# Lamp_C_Unit.net
KiCad netlist of a schematic drawn in Altium Designer
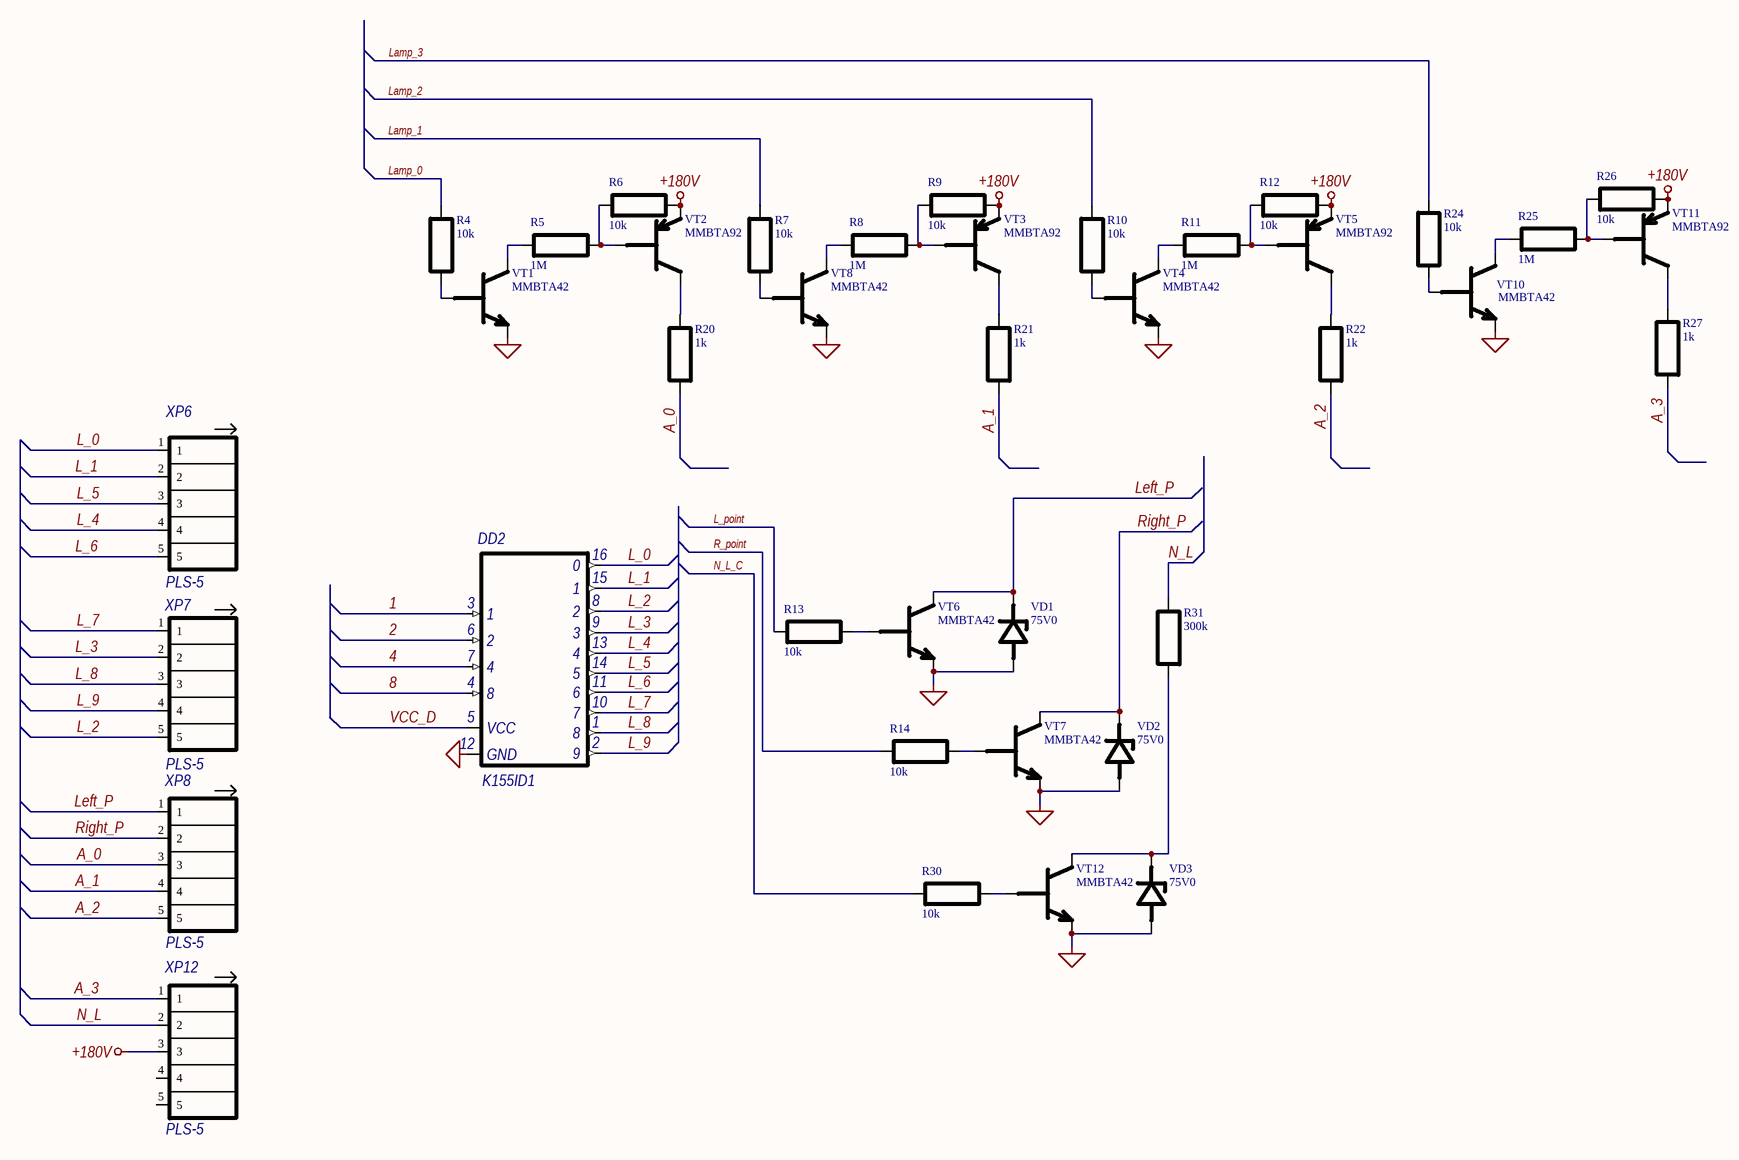
[diagram p0: Lamp_C_Unit.SchDoc]

(export (version "E")
  (design (tool "Eeschema 10.0.6"))
  (components
    (comp (ref "DD2") (value "K155ID1") (footprint "DIP16") (libsource (lib "sobol_lib") (part "K155ID1")))
    (comp (ref "R4")
      (value "10k")
      (footprint "CR2012-0805")
      (libsource (lib "sobol_lib") (part "R0805-10k-5%"))
    )
    (comp (ref "R5")
      (value "1M")
      (footprint "CR2012-0805")
      (libsource (lib "sobol_lib") (part "R0805-10k-5%"))
    )
    (comp (ref "R6")
      (value "10k")
      (footprint "CR2012-0805")
      (libsource (lib "sobol_lib") (part "R0805-10k-5%"))
    )
    (comp (ref "R7")
      (value "10k")
      (footprint "CR2012-0805")
      (libsource (lib "sobol_lib") (part "R0805-10k-5%"))
    )
    (comp (ref "R8")
      (value "1M")
      (footprint "CR2012-0805")
      (libsource (lib "sobol_lib") (part "R0805-10k-5%"))
    )
    (comp (ref "R9")
      (value "10k")
      (footprint "CR2012-0805")
      (libsource (lib "sobol_lib") (part "R0805-10k-5%"))
    )
    (comp (ref "R10")
      (value "10k")
      (footprint "CR2012-0805")
      (libsource (lib "sobol_lib") (part "R0805-10k-5%"))
    )
    (comp (ref "R11")
      (value "1M")
      (footprint "CR2012-0805")
      (libsource (lib "sobol_lib") (part "R0805-10k-5%"))
    )
    (comp (ref "R12")
      (value "10k")
      (footprint "CR2012-0805")
      (libsource (lib "sobol_lib") (part "R0805-10k-5%"))
    )
    (comp (ref "R13")
      (value "10k")
      (footprint "CR2012-0805")
      (libsource (lib "sobol_lib") (part "R0805-10k-5%"))
    )
    (comp (ref "R14")
      (value "10k")
      (footprint "CR2012-0805")
      (libsource (lib "sobol_lib") (part "R0805-10k-5%"))
    )
    (comp (ref "R20")
      (value "1k")
      (footprint "CR2012-0805")
      (libsource (lib "sobol_lib") (part "R0805-1k-5%"))
    )
    (comp (ref "R21")
      (value "1k")
      (footprint "CR2012-0805")
      (libsource (lib "sobol_lib") (part "R0805-1k-5%"))
    )
    (comp (ref "R22")
      (value "1k")
      (footprint "CR2012-0805")
      (libsource (lib "sobol_lib") (part "R0805-1k-5%"))
    )
    (comp (ref "R24")
      (value "10k")
      (footprint "CR2012-0805")
      (libsource (lib "sobol_lib") (part "R0805-10k-5%"))
    )
    (comp (ref "R25")
      (value "1M")
      (footprint "CR2012-0805")
      (libsource (lib "sobol_lib") (part "R0805-10k-5%"))
    )
    (comp (ref "R26")
      (value "10k")
      (footprint "CR2012-0805")
      (libsource (lib "sobol_lib") (part "R0805-10k-5%"))
    )
    (comp (ref "R27")
      (value "1k")
      (footprint "CR2012-0805")
      (libsource (lib "sobol_lib") (part "R0805-1k-5%"))
    )
    (comp (ref "R30")
      (value "10k")
      (footprint "CR2012-0805")
      (libsource (lib "sobol_lib") (part "R0805-10k-5%"))
    )
    (comp (ref "R31")
      (value "300k")
      (footprint "CR2012-0805")
      (libsource (lib "sobol_lib") (part "R0805-100k-5%"))
    )
    (comp (ref "VD1") (value "75V0") (footprint "SOD-80") (libsource (lib "sobol_lib") (part "BZV55-C20V0")))
    (comp (ref "VD2") (value "75V0") (footprint "SOD-80") (libsource (lib "sobol_lib") (part "BZV55-C20V0")))
    (comp (ref "VD3") (value "75V0") (footprint "SOD-80") (libsource (lib "sobol_lib") (part "BZV55-C20V0")))
    (comp (ref "VT1") (value "MMBTA42") (footprint "SOT-23") (libsource (lib "sobol_lib") (part "MMBTA42")))
    (comp (ref "VT2") (value "MMBTA92") (footprint "SOT-23") (libsource (lib "sobol_lib") (part "MMBTA92")))
    (comp (ref "VT3") (value "MMBTA92") (footprint "SOT-23") (libsource (lib "sobol_lib") (part "MMBTA92")))
    (comp (ref "VT4") (value "MMBTA42") (footprint "SOT-23") (libsource (lib "sobol_lib") (part "MMBTA42")))
    (comp (ref "VT5") (value "MMBTA92") (footprint "SOT-23") (libsource (lib "sobol_lib") (part "MMBTA92")))
    (comp (ref "VT6") (value "MMBTA42") (footprint "SOT-23") (libsource (lib "sobol_lib") (part "MMBTA42")))
    (comp (ref "VT7") (value "MMBTA42") (footprint "SOT-23") (libsource (lib "sobol_lib") (part "MMBTA42")))
    (comp (ref "VT8") (value "MMBTA42") (footprint "SOT-23") (libsource (lib "sobol_lib") (part "MMBTA42")))
    (comp (ref "VT10") (value "MMBTA42") (footprint "SOT-23") (libsource (lib "sobol_lib") (part "MMBTA42")))
    (comp (ref "VT11") (value "MMBTA92") (footprint "SOT-23") (libsource (lib "sobol_lib") (part "MMBTA92")))
    (comp (ref "VT12") (value "MMBTA42") (footprint "SOT-23") (libsource (lib "sobol_lib") (part "MMBTA42")))
    (comp (ref "XP6") (value "PLS-5") (footprint "PLS-5") (libsource (lib "sobol_lib") (part "PLS-5")))
    (comp (ref "XP7") (value "PLS-5") (footprint "PLS-5") (libsource (lib "sobol_lib") (part "PLS-5")))
    (comp (ref "XP8") (value "PLS-5") (footprint "PLS-5") (libsource (lib "sobol_lib") (part "PLS-5")))
    (comp (ref "XP12") (value "PLS-5") (footprint "PLS-5") (libsource (lib "sobol_lib") (part "PLS-5")))
  )
  (nets
    (net (code "1") (name "+180V") (class "Default")
      (node (ref "R12") (pin "2") (pinfunction "2_2") (pintype "passive"))
      (node (ref "R26") (pin "2") (pinfunction "2_2") (pintype "passive"))
      (node (ref "R6") (pin "2") (pinfunction "2_2") (pintype "passive"))
      (node (ref "R9") (pin "2") (pinfunction "2_2") (pintype "passive"))
      (node (ref "VT11") (pin "2") (pinfunction "E_2") (pintype "passive"))
      (node (ref "VT2") (pin "2") (pinfunction "E_2") (pintype "passive"))
      (node (ref "VT3") (pin "2") (pinfunction "E_2") (pintype "passive"))
      (node (ref "VT5") (pin "2") (pinfunction "E_2") (pintype "passive"))
      (node (ref "XP12") (pin "3") (pinfunction "3_3") (pintype "passive"))
    )
    (net (code "2") (name "/1") (class "Default")
      (node (ref "DD2") (pin "3") (pinfunction "1_3") (pintype "input"))
    )
    (net (code "3") (name "/2") (class "Default")
      (node (ref "DD2") (pin "6") (pinfunction "2_6") (pintype "input"))
    )
    (net (code "4") (name "/4") (class "Default")
      (node (ref "DD2") (pin "7") (pinfunction "4_7") (pintype "input"))
    )
    (net (code "5") (name "/8") (class "Default")
      (node (ref "DD2") (pin "4") (pinfunction "8_4") (pintype "input"))
    )
    (net (code "6") (name "/A_0") (class "Default")
      (node (ref "R20") (pin "1") (pinfunction "1_1") (pintype "passive"))
      (node (ref "XP8") (pin "3") (pinfunction "3_3") (pintype "passive"))
    )
    (net (code "7") (name "/A_1") (class "Default")
      (node (ref "R21") (pin "1") (pinfunction "1_1") (pintype "passive"))
      (node (ref "XP8") (pin "4") (pinfunction "4_4") (pintype "passive"))
    )
    (net (code "8") (name "/A_2") (class "Default")
      (node (ref "R22") (pin "1") (pinfunction "1_1") (pintype "passive"))
      (node (ref "XP8") (pin "5") (pinfunction "5_5") (pintype "passive"))
    )
    (net (code "9") (name "/A_3") (class "Default")
      (node (ref "R27") (pin "1") (pinfunction "1_1") (pintype "passive"))
      (node (ref "XP12") (pin "1") (pinfunction "1_1") (pintype "passive"))
    )
    (net (code "10") (name "/L_0") (class "Default")
      (node (ref "DD2") (pin "16") (pinfunction "0_16") (pintype "output"))
      (node (ref "XP6") (pin "1") (pinfunction "1_1") (pintype "passive"))
    )
    (net (code "11") (name "/L_1") (class "Default")
      (node (ref "DD2") (pin "15") (pinfunction "1_15") (pintype "output"))
      (node (ref "XP6") (pin "2") (pinfunction "2_2") (pintype "passive"))
    )
    (net (code "12") (name "/L_2") (class "Default")
      (node (ref "DD2") (pin "8") (pinfunction "2_8") (pintype "output"))
      (node (ref "XP7") (pin "5") (pinfunction "5_5") (pintype "passive"))
    )
    (net (code "13") (name "/L_3") (class "Default")
      (node (ref "DD2") (pin "9") (pinfunction "3_9") (pintype "output"))
      (node (ref "XP7") (pin "2") (pinfunction "2_2") (pintype "passive"))
    )
    (net (code "14") (name "/L_4") (class "Default")
      (node (ref "DD2") (pin "13") (pinfunction "4_13") (pintype "output"))
      (node (ref "XP6") (pin "4") (pinfunction "4_4") (pintype "passive"))
    )
    (net (code "15") (name "/L_5") (class "Default")
      (node (ref "DD2") (pin "14") (pinfunction "5_14") (pintype "output"))
      (node (ref "XP6") (pin "3") (pinfunction "3_3") (pintype "passive"))
    )
    (net (code "16") (name "/L_6") (class "Default")
      (node (ref "DD2") (pin "11") (pinfunction "6_11") (pintype "output"))
      (node (ref "XP6") (pin "5") (pinfunction "5_5") (pintype "passive"))
    )
    (net (code "17") (name "/L_7") (class "Default")
      (node (ref "DD2") (pin "10") (pinfunction "7_10") (pintype "output"))
      (node (ref "XP7") (pin "1") (pinfunction "1_1") (pintype "passive"))
    )
    (net (code "18") (name "/L_8") (class "Default")
      (node (ref "DD2") (pin "1") (pinfunction "8_1") (pintype "output"))
      (node (ref "XP7") (pin "3") (pinfunction "3_3") (pintype "passive"))
    )
    (net (code "19") (name "/L_9") (class "Default")
      (node (ref "DD2") (pin "2") (pinfunction "9_2") (pintype "output"))
      (node (ref "XP7") (pin "4") (pinfunction "4_4") (pintype "passive"))
    )
    (net (code "20") (name "/L_point") (class "Default")
      (node (ref "R13") (pin "1") (pinfunction "1_1") (pintype "passive"))
    )
    (net (code "21") (name "/Lamp_0") (class "Default")
      (node (ref "R4") (pin "1") (pinfunction "1_1") (pintype "passive"))
    )
    (net (code "22") (name "/Lamp_1") (class "Default")
      (node (ref "R7") (pin "1") (pinfunction "1_1") (pintype "passive"))
    )
    (net (code "23") (name "/Lamp_2") (class "Default")
      (node (ref "R10") (pin "1") (pinfunction "1_1") (pintype "passive"))
    )
    (net (code "24") (name "/Lamp_3") (class "Default")
      (node (ref "R24") (pin "1") (pinfunction "1_1") (pintype "passive"))
    )
    (net (code "25") (name "/Left_P") (class "Default")
      (node (ref "VD1") (pin "2") (pinfunction "K_2") (pintype "passive"))
      (node (ref "VT6") (pin "3") (pinfunction "C_3") (pintype "passive"))
      (node (ref "XP8") (pin "1") (pinfunction "1_1") (pintype "passive"))
    )
    (net (code "26") (name "/N_L") (class "Default")
      (node (ref "R31") (pin "2") (pinfunction "2_2") (pintype "passive"))
      (node (ref "XP12") (pin "2") (pinfunction "2_2") (pintype "passive"))
    )
    (net (code "27") (name "/N_L_C") (class "Default")
      (node (ref "R30") (pin "1") (pinfunction "1_1") (pintype "passive"))
    )
    (net (code "28") (name "/R_point") (class "Default")
      (node (ref "R14") (pin "1") (pinfunction "1_1") (pintype "passive"))
    )
    (net (code "29") (name "/Right_P") (class "Default")
      (node (ref "VD2") (pin "2") (pinfunction "K_2") (pintype "passive"))
      (node (ref "VT7") (pin "3") (pinfunction "C_3") (pintype "passive"))
      (node (ref "XP8") (pin "2") (pinfunction "2_2") (pintype "passive"))
    )
    (net (code "30") (name "/VCC_D") (class "Default")
      (node (ref "DD2") (pin "5") (pinfunction "VCC_5") (pintype "power_in"))
    )
    (net (code "31") (name "Net-(VD3-K)") (class "Default")
      (node (ref "R31") (pin "1") (pinfunction "1_1") (pintype "passive"))
      (node (ref "VD3") (pin "2") (pinfunction "K_2") (pintype "passive"))
      (node (ref "VT12") (pin "3") (pinfunction "C_3") (pintype "passive"))
    )
    (net (code "32") (name "Net-(VT1-B)") (class "Default")
      (node (ref "R4") (pin "2") (pinfunction "2_2") (pintype "passive"))
      (node (ref "VT1") (pin "1") (pinfunction "B_1") (pintype "passive"))
    )
    (net (code "33") (name "Net-(VT1-C)") (class "Default")
      (node (ref "R5") (pin "1") (pinfunction "1_1") (pintype "passive"))
      (node (ref "VT1") (pin "3") (pinfunction "C_3") (pintype "passive"))
    )
    (net (code "34") (name "Net-(VT2-B)") (class "Default")
      (node (ref "R5") (pin "2") (pinfunction "2_2") (pintype "passive"))
      (node (ref "R6") (pin "1") (pinfunction "1_1") (pintype "passive"))
      (node (ref "VT2") (pin "1") (pinfunction "B_1") (pintype "passive"))
    )
    (net (code "35") (name "Net-(VT2-C)") (class "Default")
      (node (ref "R20") (pin "2") (pinfunction "2_2") (pintype "passive"))
      (node (ref "VT2") (pin "3") (pinfunction "C_3") (pintype "passive"))
    )
    (net (code "36") (name "Net-(VT3-B)") (class "Default")
      (node (ref "R8") (pin "2") (pinfunction "2_2") (pintype "passive"))
      (node (ref "R9") (pin "1") (pinfunction "1_1") (pintype "passive"))
      (node (ref "VT3") (pin "1") (pinfunction "B_1") (pintype "passive"))
    )
    (net (code "37") (name "Net-(VT3-C)") (class "Default")
      (node (ref "R21") (pin "2") (pinfunction "2_2") (pintype "passive"))
      (node (ref "VT3") (pin "3") (pinfunction "C_3") (pintype "passive"))
    )
    (net (code "38") (name "Net-(VT4-B)") (class "Default")
      (node (ref "R10") (pin "2") (pinfunction "2_2") (pintype "passive"))
      (node (ref "VT4") (pin "1") (pinfunction "B_1") (pintype "passive"))
    )
    (net (code "39") (name "Net-(VT4-C)") (class "Default")
      (node (ref "R11") (pin "1") (pinfunction "1_1") (pintype "passive"))
      (node (ref "VT4") (pin "3") (pinfunction "C_3") (pintype "passive"))
    )
    (net (code "40") (name "Net-(VT5-B)") (class "Default")
      (node (ref "R11") (pin "2") (pinfunction "2_2") (pintype "passive"))
      (node (ref "R12") (pin "1") (pinfunction "1_1") (pintype "passive"))
      (node (ref "VT5") (pin "1") (pinfunction "B_1") (pintype "passive"))
    )
    (net (code "41") (name "Net-(VT5-C)") (class "Default")
      (node (ref "R22") (pin "2") (pinfunction "2_2") (pintype "passive"))
      (node (ref "VT5") (pin "3") (pinfunction "C_3") (pintype "passive"))
    )
    (net (code "42") (name "Net-(VT6-B)") (class "Default")
      (node (ref "R13") (pin "2") (pinfunction "2_2") (pintype "passive"))
      (node (ref "VT6") (pin "1") (pinfunction "B_1") (pintype "passive"))
    )
    (net (code "43") (name "Net-(VT7-B)") (class "Default")
      (node (ref "R14") (pin "2") (pinfunction "2_2") (pintype "passive"))
      (node (ref "VT7") (pin "1") (pinfunction "B_1") (pintype "passive"))
    )
    (net (code "44") (name "Net-(VT8-B)") (class "Default")
      (node (ref "R7") (pin "2") (pinfunction "2_2") (pintype "passive"))
      (node (ref "VT8") (pin "1") (pinfunction "B_1") (pintype "passive"))
    )
    (net (code "45") (name "Net-(VT8-C)") (class "Default")
      (node (ref "R8") (pin "1") (pinfunction "1_1") (pintype "passive"))
      (node (ref "VT8") (pin "3") (pinfunction "C_3") (pintype "passive"))
    )
    (net (code "46") (name "Net-(VT10-B)") (class "Default")
      (node (ref "R24") (pin "2") (pinfunction "2_2") (pintype "passive"))
      (node (ref "VT10") (pin "1") (pinfunction "B_1") (pintype "passive"))
    )
    (net (code "47") (name "Net-(VT10-C)") (class "Default")
      (node (ref "R25") (pin "1") (pinfunction "1_1") (pintype "passive"))
      (node (ref "VT10") (pin "3") (pinfunction "C_3") (pintype "passive"))
    )
    (net (code "48") (name "Net-(VT11-B)") (class "Default")
      (node (ref "R25") (pin "2") (pinfunction "2_2") (pintype "passive"))
      (node (ref "R26") (pin "1") (pinfunction "1_1") (pintype "passive"))
      (node (ref "VT11") (pin "1") (pinfunction "B_1") (pintype "passive"))
    )
    (net (code "49") (name "Net-(VT11-C)") (class "Default")
      (node (ref "R27") (pin "2") (pinfunction "2_2") (pintype "passive"))
      (node (ref "VT11") (pin "3") (pinfunction "C_3") (pintype "passive"))
    )
    (net (code "50") (name "Net-(VT12-B)") (class "Default")
      (node (ref "R30") (pin "2") (pinfunction "2_2") (pintype "passive"))
      (node (ref "VT12") (pin "1") (pinfunction "B_1") (pintype "passive"))
    )
    (net (code "51") (name "SGND") (class "Default")
      (node (ref "DD2") (pin "12") (pinfunction "GND_12") (pintype "power_in"))
      (node (ref "VD1") (pin "1") (pinfunction "A_1") (pintype "passive"))
      (node (ref "VD2") (pin "1") (pinfunction "A_1") (pintype "passive"))
      (node (ref "VD3") (pin "1") (pinfunction "A_1") (pintype "passive"))
      (node (ref "VT1") (pin "2") (pinfunction "E_2") (pintype "passive"))
      (node (ref "VT10") (pin "2") (pinfunction "E_2") (pintype "passive"))
      (node (ref "VT12") (pin "2") (pinfunction "E_2") (pintype "passive"))
      (node (ref "VT4") (pin "2") (pinfunction "E_2") (pintype "passive"))
      (node (ref "VT6") (pin "2") (pinfunction "E_2") (pintype "passive"))
      (node (ref "VT7") (pin "2") (pinfunction "E_2") (pintype "passive"))
      (node (ref "VT8") (pin "2") (pinfunction "E_2") (pintype "passive"))
    )
    (net (code "52") (name "unconnected-(XP12-Pad4)") (class "Default")
      (node (ref "XP12") (pin "4") (pinfunction "4_4") (pintype "passive"))
    )
    (net (code "53") (name "unconnected-(XP12-Pad5)") (class "Default")
      (node (ref "XP12") (pin "5") (pinfunction "5_5") (pintype "passive"))
    )
  )
)
